# 2_PowerPerif.net
KiCad netlist of a schematic drawn in Altium Designer
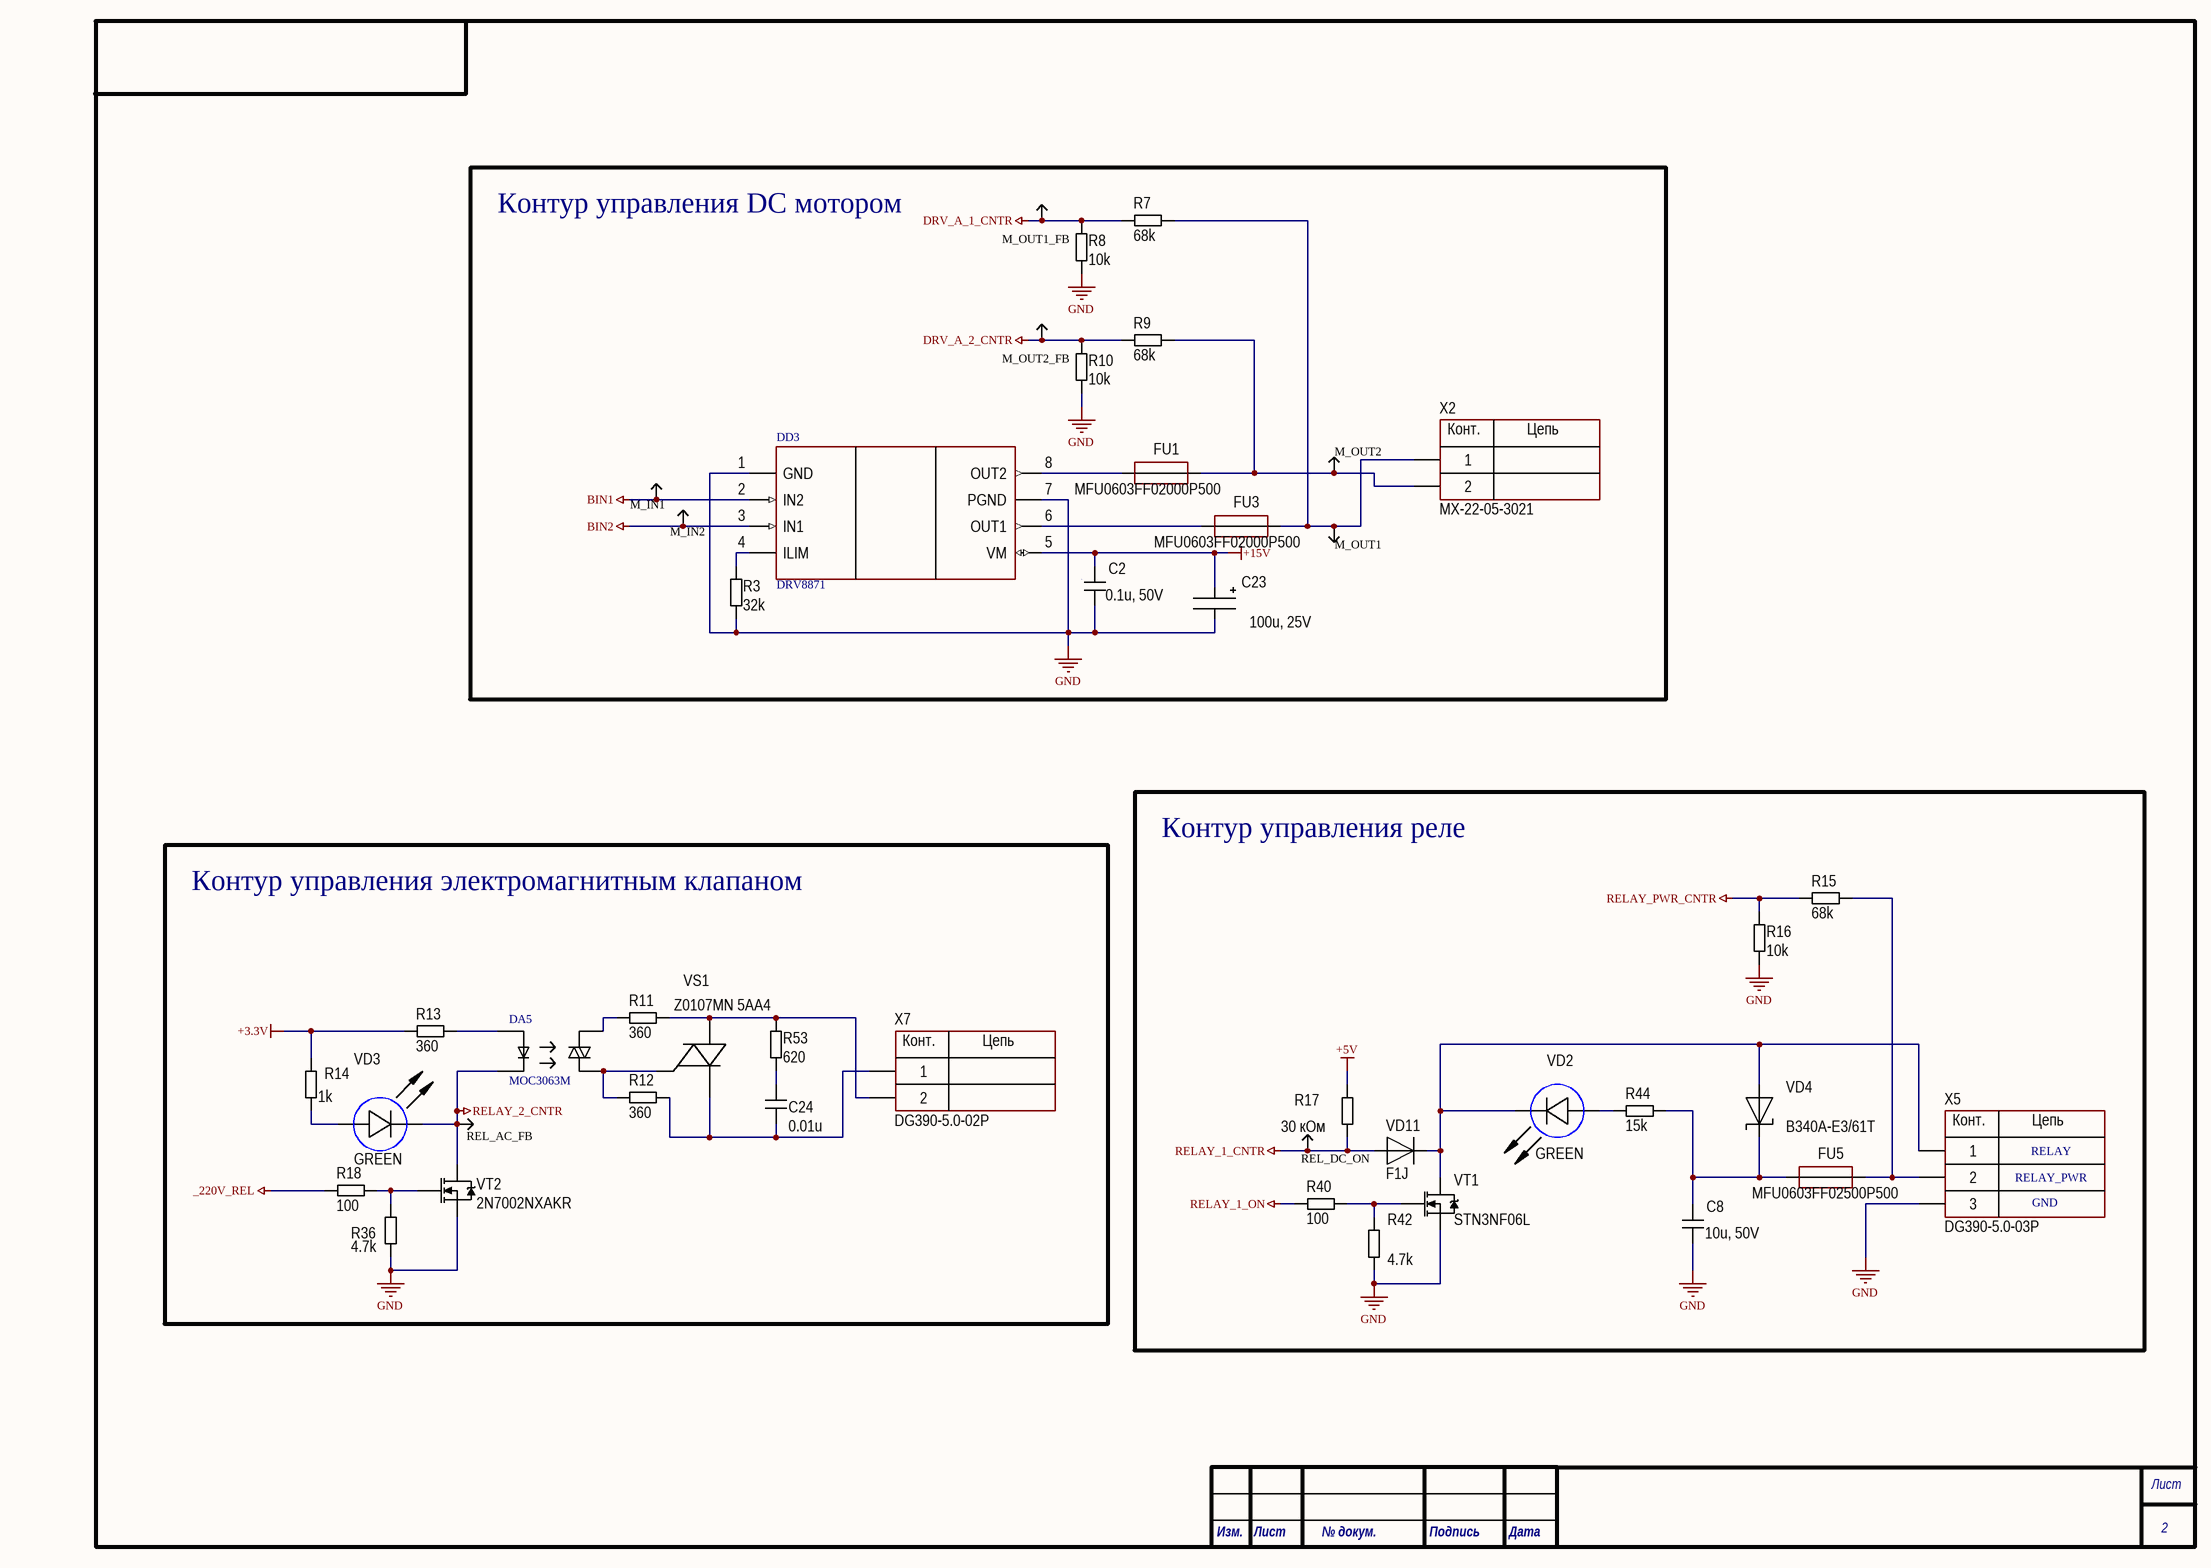
[diagram p0: 2_PowerPerif.SchDoc]

(export (version "E")
  (design (tool "Eeschema 10.0.6"))
  (components
    (comp (ref "C2")
      (value "0.1u, 50V")
      (footprint "CH0402C")
      (libsource (lib "Condensators") (part "Capacitor"))
    )
    (comp (ref "C8")
      (value "10u, 50V")
      (footprint "CH1206C")
      (libsource (lib "Condensators") (part "Capacitor"))
    )
    (comp (ref "C23")
      (value "100u, 25V")
      (footprint "D6.6C6.6H6.1")
      (libsource (lib "Condensators") (part "AlumCap"))
    )
    (comp (ref "C24")
      (value "0.01u")
      (footprint "CH1210C")
      (libsource (lib "Condensators") (part "Capacitor"))
    )
    (comp (ref "DA5") (value "MOC3063M") (footprint "DIP6") (libsource (lib "MicroIC") (part "MOC3063")))
    (comp (ref "DD3") (value "DRV8871") (footprint "8-HSOP") (libsource (lib "MicroIC") (part "DRV8871")))
    (comp (ref "FU1")
      (value "MFU0603FF02000P500")
      (footprint "CH0603F")
      (libsource (lib "Melochi") (part "Fuse"))
    )
    (comp (ref "FU3")
      (value "MFU0603FF02000P500")
      (footprint "CH0603F")
      (libsource (lib "Melochi") (part "Fuse"))
    )
    (comp (ref "FU5")
      (value "MFU0603FF02500P500")
      (footprint "CH0603F")
      (libsource (lib "Melochi") (part "Fuse"))
    )
    (comp (ref "M_IN1") (value "~") (footprint "TestPoint") (libsource (lib "Melochi") (part "TestPoint")))
    (comp (ref "M_IN2") (value "~") (footprint "TestPoint") (libsource (lib "Melochi") (part "TestPoint")))
    (comp (ref "M_OUT1") (value "~") (footprint "TestPoint") (libsource (lib "Melochi") (part "TestPoint")))
    (comp (ref "M_OUT1_FB")
      (value "~")
      (footprint "TestPoint")
      (libsource (lib "Melochi") (part "TestPoint"))
    )
    (comp (ref "M_OUT2") (value "~") (footprint "TestPoint") (libsource (lib "Melochi") (part "TestPoint")))
    (comp (ref "M_OUT2_FB")
      (value "~")
      (footprint "TestPoint")
      (libsource (lib "Melochi") (part "TestPoint"))
    )
    (comp (ref "R3") (value "32k") (footprint "CH0603R") (libsource (lib "Resistors") (part "Resistor")))
    (comp (ref "R7") (value "68k") (footprint "CH0402R") (libsource (lib "Resistors") (part "Resistor")))
    (comp (ref "R8") (value "10k") (footprint "CH0402R") (libsource (lib "Resistors") (part "Resistor")))
    (comp (ref "R9") (value "68k") (footprint "CH0402R") (libsource (lib "Resistors") (part "Resistor")))
    (comp (ref "R10") (value "10k") (footprint "CH0402R") (libsource (lib "Resistors") (part "Resistor")))
    (comp (ref "R11") (value "360") (footprint "CH2010R") (libsource (lib "Resistors") (part "Resistor")))
    (comp (ref "R12") (value "360") (footprint "CH2010R") (libsource (lib "Resistors") (part "Resistor")))
    (comp (ref "R13") (value "360") (footprint "CH0805R") (libsource (lib "Resistors") (part "Resistor")))
    (comp (ref "R14") (value "1k") (footprint "CH0805R") (libsource (lib "Resistors") (part "Resistor")))
    (comp (ref "R15") (value "68k") (footprint "CH0402R") (libsource (lib "Resistors") (part "Resistor")))
    (comp (ref "R16") (value "10k") (footprint "CH0402R") (libsource (lib "Resistors") (part "Resistor")))
    (comp (ref "R17") (value "30 кОм") (footprint "CH0402R") (libsource (lib "Resistors") (part "Resistor")))
    (comp (ref "R18") (value "100") (footprint "CH0805R") (libsource (lib "Resistors") (part "Resistor")))
    (comp (ref "R36") (value "4.7k") (footprint "CH0402R") (libsource (lib "Resistors") (part "Resistor")))
    (comp (ref "R40") (value "100") (footprint "CH0805R") (libsource (lib "Resistors") (part "Resistor")))
    (comp (ref "R42") (value "4.7k") (footprint "CH0402R") (libsource (lib "Resistors") (part "Resistor")))
    (comp (ref "R44") (value "15k") (footprint "CH0805R") (libsource (lib "Resistors") (part "Resistor")))
    (comp (ref "R53") (value "620") (footprint "CH2010R") (libsource (lib "Resistors") (part "Resistor")))
    (comp (ref "REL_AC_FB")
      (value "~")
      (footprint "TestPoint")
      (libsource (lib "Melochi") (part "TestPoint"))
    )
    (comp (ref "REL_DC_ON")
      (value "~")
      (footprint "TestPoint")
      (libsource (lib "Melochi") (part "TestPoint"))
    )
    (comp (ref "VD2") (value "GREEN") (footprint "CH0603LB") (libsource (lib "Diods") (part "LED_1")))
    (comp (ref "VD3") (value "GREEN") (footprint "CH0603LB") (libsource (lib "Diods") (part "LED_1")))
    (comp (ref "VD4")
      (value "B340A-E3/61T")
      (footprint "SMA")
      (libsource (lib "Diods") (part "Diod Schottky"))
    )
    (comp (ref "VD11") (value "F1J") (footprint "SOD123F") (libsource (lib "Diods") (part "Diod")))
    (comp (ref "VS1")
      (value "Z0107MN 5AA4")
      (footprint "SOT223_G-D-S")
      (description "Bipolar")
      (libsource (lib "Tranzistor") (part "TRIAC"))
    )
    (comp (ref "VT1")
      (value "STN3NF06L")
      (footprint "SOT223_G-D-S")
      (description "Mosfet")
      (libsource (lib "Tranzistor") (part "N-chanel"))
    )
    (comp (ref "VT2")
      (value "2N7002NXAKR")
      (footprint "SOT23_123")
      (description "Mosfet")
      (libsource (lib "Tranzistor") (part "N-chanel"))
    )
    (comp (ref "X2")
      (value "MX-22-05-3021")
      (footprint "CON: MX-22-05-3021")
      (libsource (lib "Connectors") (part "2-Connector"))
    )
    (comp (ref "X5")
      (value "DG390-5.0-03P")
      (footprint "CON: 300-03P-5.0")
      (libsource (lib "Connectors") (part "3-Connector"))
    )
    (comp (ref "X7")
      (value "DG390-5.0-02P")
      (footprint "CON: 300-02P-5.0")
      (libsource (lib "Connectors") (part "2-Connector"))
    )
  )
  (nets
    (net (code "1") (name "+3.3V") (class "Default")
      (node (ref "R13") (pin "2") (pinfunction "2_2") (pintype "passive"))
      (node (ref "R14") (pin "2") (pinfunction "2_2") (pintype "passive"))
    )
    (net (code "2") (name "+5V") (class "Default")
      (node (ref "R17") (pin "2") (pinfunction "2_2") (pintype "passive"))
    )
    (net (code "3") (name "+15V") (class "Default")
      (node (ref "C2") (pin "2") (pinfunction "2_2") (pintype "passive"))
      (node (ref "C23") (pin "1") (pinfunction "1_1") (pintype "power_in"))
      (node (ref "DD3") (pin "5") (pinfunction "VM_5") (pintype "bidirectional"))
    )
    (net (code "4") (name "BIN1") (class "Default")
      (node (ref "DD3") (pin "2") (pinfunction "IN2_2") (pintype "input"))
      (node (ref "M_IN1") (pin "0") (pinfunction "0_0") (pintype "passive"))
    )
    (net (code "5") (name "BIN2") (class "Default")
      (node (ref "DD3") (pin "3") (pinfunction "IN1_3") (pintype "input"))
      (node (ref "M_IN2") (pin "0") (pinfunction "0_0") (pintype "passive"))
    )
    (net (code "6") (name "DRV_A_1_CNTR") (class "Default")
      (node (ref "M_OUT1_FB") (pin "0") (pinfunction "0_0") (pintype "passive"))
      (node (ref "R7") (pin "2") (pinfunction "2_2") (pintype "passive"))
      (node (ref "R8") (pin "2") (pinfunction "2_2") (pintype "passive"))
    )
    (net (code "7") (name "DRV_A_2_CNTR") (class "Default")
      (node (ref "M_OUT2_FB") (pin "0") (pinfunction "0_0") (pintype "passive"))
      (node (ref "R10") (pin "2") (pinfunction "2_2") (pintype "passive"))
      (node (ref "R9") (pin "2") (pinfunction "2_2") (pintype "passive"))
    )
    (net (code "8") (name "GND") (class "Default")
      (node (ref "C2") (pin "1") (pinfunction "1_1") (pintype "passive"))
      (node (ref "C23") (pin "2") (pinfunction "2_2") (pintype "power_in"))
      (node (ref "C8") (pin "1") (pinfunction "1_1") (pintype "passive"))
      (node (ref "DD3") (pin "1") (pinfunction "GND_1") (pintype "power_in"))
      (node (ref "DD3") (pin "7") (pinfunction "PGND_7") (pintype "power_in"))
      (node (ref "R10") (pin "1") (pinfunction "1_1") (pintype "passive"))
      (node (ref "R16") (pin "1") (pinfunction "1_1") (pintype "passive"))
      (node (ref "R3") (pin "1") (pinfunction "1_1") (pintype "passive"))
      (node (ref "R36") (pin "1") (pinfunction "1_1") (pintype "passive"))
      (node (ref "R42") (pin "1") (pinfunction "1_1") (pintype "passive"))
      (node (ref "R8") (pin "1") (pinfunction "1_1") (pintype "passive"))
      (node (ref "VT1") (pin "3") (pinfunction "S_3") (pintype "passive"))
      (node (ref "VT2") (pin "3") (pinfunction "S_3") (pintype "passive"))
      (node (ref "X5") (pin "3") (pinfunction "3_3") (pintype "passive"))
    )
    (net (code "9") (name "Net-(C8-Pad2)") (class "Default")
      (node (ref "C8") (pin "2") (pinfunction "2_2") (pintype "passive"))
      (node (ref "FU5") (pin "1") (pinfunction "1_1") (pintype "passive"))
      (node (ref "R44") (pin "2") (pinfunction "2_2") (pintype "passive"))
      (node (ref "VD4") (pin "2") (pinfunction "2_2") (pintype "passive"))
    )
    (net (code "10") (name "Net-(C24-Pad1)") (class "Default")
      (node (ref "C24") (pin "1") (pinfunction "1_1") (pintype "passive"))
      (node (ref "R12") (pin "1") (pinfunction "1_1") (pintype "passive"))
      (node (ref "VS1") (pin "1") (pinfunction "1_1") (pintype "passive"))
      (node (ref "X7") (pin "1") (pinfunction "1_1") (pintype "passive"))
    )
    (net (code "11") (name "Net-(C24-Pad2)") (class "Default")
      (node (ref "C24") (pin "2") (pinfunction "2_2") (pintype "passive"))
      (node (ref "R53") (pin "2") (pinfunction "2_2") (pintype "passive"))
    )
    (net (code "12") (name "Net-(DA5-Pad4)") (class "Default")
      (node (ref "DA5") (pin "4") (pinfunction "4_4") (pintype "passive"))
      (node (ref "R11") (pin "2") (pinfunction "2_2") (pintype "passive"))
    )
    (net (code "13") (name "Net-(DA5-Pad6)") (class "Default")
      (node (ref "DA5") (pin "6") (pinfunction "6_6") (pintype "passive"))
      (node (ref "R12") (pin "2") (pinfunction "2_2") (pintype "passive"))
      (node (ref "VS1") (pin "3") (pinfunction "3_3") (pintype "passive"))
    )
    (net (code "14") (name "Net-(DA5-Vpr+)") (class "Default")
      (node (ref "DA5") (pin "1") (pinfunction "Vpr+_1") (pintype "passive"))
      (node (ref "R13") (pin "1") (pinfunction "1_1") (pintype "passive"))
    )
    (net (code "15") (name "Net-(DD3-ILIM)") (class "Default")
      (node (ref "DD3") (pin "4") (pinfunction "ILIM_4") (pintype "passive"))
      (node (ref "R3") (pin "2") (pinfunction "2_2") (pintype "passive"))
    )
    (net (code "16") (name "Net-(DD3-OUT1)") (class "Default")
      (node (ref "DD3") (pin "6") (pinfunction "OUT1_6") (pintype "output"))
      (node (ref "FU3") (pin "1") (pinfunction "1_1") (pintype "passive"))
    )
    (net (code "17") (name "Net-(DD3-OUT2)") (class "Default")
      (node (ref "DD3") (pin "8") (pinfunction "OUT2_8") (pintype "output"))
      (node (ref "FU1") (pin "1") (pinfunction "1_1") (pintype "passive"))
    )
    (net (code "18") (name "Net-(FU1-Pad2)") (class "Default")
      (node (ref "FU1") (pin "2") (pinfunction "2_2") (pintype "passive"))
      (node (ref "M_OUT2") (pin "0") (pinfunction "0_0") (pintype "passive"))
      (node (ref "R9") (pin "1") (pinfunction "1_1") (pintype "passive"))
      (node (ref "X2") (pin "2") (pinfunction "2_2") (pintype "passive"))
    )
    (net (code "19") (name "Net-(FU3-Pad2)") (class "Default")
      (node (ref "FU3") (pin "2") (pinfunction "2_2") (pintype "passive"))
      (node (ref "M_OUT1") (pin "0") (pinfunction "0_0") (pintype "passive"))
      (node (ref "R7") (pin "1") (pinfunction "1_1") (pintype "passive"))
      (node (ref "X2") (pin "1") (pinfunction "1_1") (pintype "passive"))
    )
    (net (code "20") (name "Net-(FU5-Pad2)") (class "Default")
      (node (ref "FU5") (pin "2") (pinfunction "2_2") (pintype "passive"))
      (node (ref "R15") (pin "1") (pinfunction "1_1") (pintype "passive"))
      (node (ref "X5") (pin "2") (pinfunction "2_2") (pintype "passive"))
    )
    (net (code "21") (name "Net-(R11-Pad1)") (class "Default")
      (node (ref "R11") (pin "1") (pinfunction "1_1") (pintype "passive"))
      (node (ref "R53") (pin "1") (pinfunction "1_1") (pintype "passive"))
      (node (ref "VS1") (pin "2") (pinfunction "2_2") (pintype "passive"))
      (node (ref "X7") (pin "2") (pinfunction "2_2") (pintype "passive"))
    )
    (net (code "22") (name "Net-(VD2-A)") (class "Default")
      (node (ref "R44") (pin "1") (pinfunction "1_1") (pintype "passive"))
      (node (ref "VD2") (pin "1") (pinfunction "A_1") (pintype "passive"))
    )
    (net (code "23") (name "Net-(VD2-C)") (class "Default")
      (node (ref "VD11") (pin "2") (pinfunction "2_2") (pintype "passive"))
      (node (ref "VD2") (pin "2") (pinfunction "C_2") (pintype "passive"))
      (node (ref "VD4") (pin "1") (pinfunction "1_1") (pintype "passive"))
      (node (ref "VT1") (pin "2") (pinfunction "D_2") (pintype "passive"))
      (node (ref "X5") (pin "1") (pinfunction "1_1") (pintype "passive"))
    )
    (net (code "24") (name "Net-(VD3-A)") (class "Default")
      (node (ref "R14") (pin "1") (pinfunction "1_1") (pintype "passive"))
      (node (ref "VD3") (pin "1") (pinfunction "A_1") (pintype "passive"))
    )
    (net (code "25") (name "Net-(VT1-G)") (class "Default")
      (node (ref "R40") (pin "1") (pinfunction "1_1") (pintype "passive"))
      (node (ref "R42") (pin "2") (pinfunction "2_2") (pintype "passive"))
      (node (ref "VT1") (pin "1") (pinfunction "G_1") (pintype "passive"))
    )
    (net (code "26") (name "Net-(VT2-G)") (class "Default")
      (node (ref "R18") (pin "1") (pinfunction "1_1") (pintype "passive"))
      (node (ref "R36") (pin "2") (pinfunction "2_2") (pintype "passive"))
      (node (ref "VT2") (pin "1") (pinfunction "G_1") (pintype "passive"))
    )
    (net (code "27") (name "RELAY_1_CNTR") (class "Default")
      (node (ref "R17") (pin "1") (pinfunction "1_1") (pintype "passive"))
      (node (ref "REL_DC_ON") (pin "0") (pinfunction "0_0") (pintype "passive"))
      (node (ref "VD11") (pin "1") (pinfunction "1_1") (pintype "passive"))
    )
    (net (code "28") (name "RELAY_1_ON") (class "Default")
      (node (ref "R40") (pin "2") (pinfunction "2_2") (pintype "passive"))
    )
    (net (code "29") (name "RELAY_2_CNTR") (class "Default")
      (node (ref "DA5") (pin "2") (pinfunction "Vpr-_2") (pintype "passive"))
      (node (ref "REL_AC_FB") (pin "0") (pinfunction "0_0") (pintype "passive"))
      (node (ref "VD3") (pin "2") (pinfunction "C_2") (pintype "passive"))
      (node (ref "VT2") (pin "2") (pinfunction "D_2") (pintype "passive"))
    )
    (net (code "30") (name "RELAY_PWR_CNTR") (class "Default")
      (node (ref "R15") (pin "2") (pinfunction "2_2") (pintype "passive"))
      (node (ref "R16") (pin "2") (pinfunction "2_2") (pintype "passive"))
    )
    (net (code "31") (name "_220V_REL") (class "Default")
      (node (ref "R18") (pin "2") (pinfunction "2_2") (pintype "passive"))
    )
  )
)
